# QCopterFC_KEY_Sch.net
KiCad netlist of a schematic drawn in Altium Designer
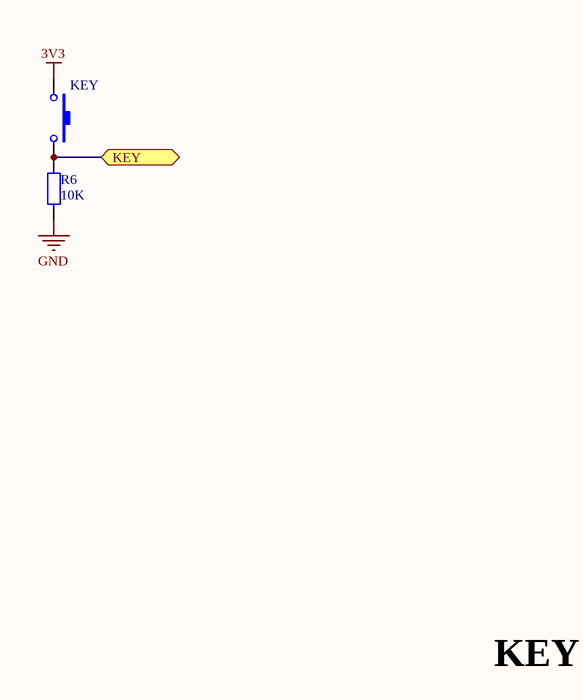
[diagram p0: QCopterFC_KEY_Sch.SchDoc]

(export (version "E")
  (design (tool "Eeschema 10.0.6"))
  (components
    (comp (ref "KEY")
      (value "SW-PB_1")
      (footprint "PCB_Switch:BT_90_T")
      (description "Switch")
      (fields (field (name "PUBLISHER") "Altium Limited"))
      (libsource (lib "SCH_Switch") (part "SW-PB_1"))
    )
    (comp (ref "R6")
      (value "10K")
      (footprint "PCB_Passive:RES_0603")
      (description "Resistor")
      (fields (field (name "Comment") "Res_0603"))
      (libsource (lib "SCH_Passive") (part "Res_0603"))
    )
  )
  (nets
    (net (code "1") (name "/KEY") (class "Default")
      (node (ref "KEY") (pin "2") (pinfunction "2_2") (pintype "passive"))
      (node (ref "R6") (pin "2") (pinfunction "2_2") (pintype "passive"))
    )
    (net (code "2") (name "3V3") (class "Default")
      (node (ref "KEY") (pin "1") (pinfunction "1_1") (pintype "passive"))
    )
    (net (code "3") (name "GND") (class "Default")
      (node (ref "R6") (pin "1") (pinfunction "1_1") (pintype "passive"))
    )
  )
)
